# BOTTOM_BRD_v_0_1_0.net
KiCad netlist of a schematic drawn in EAGLE
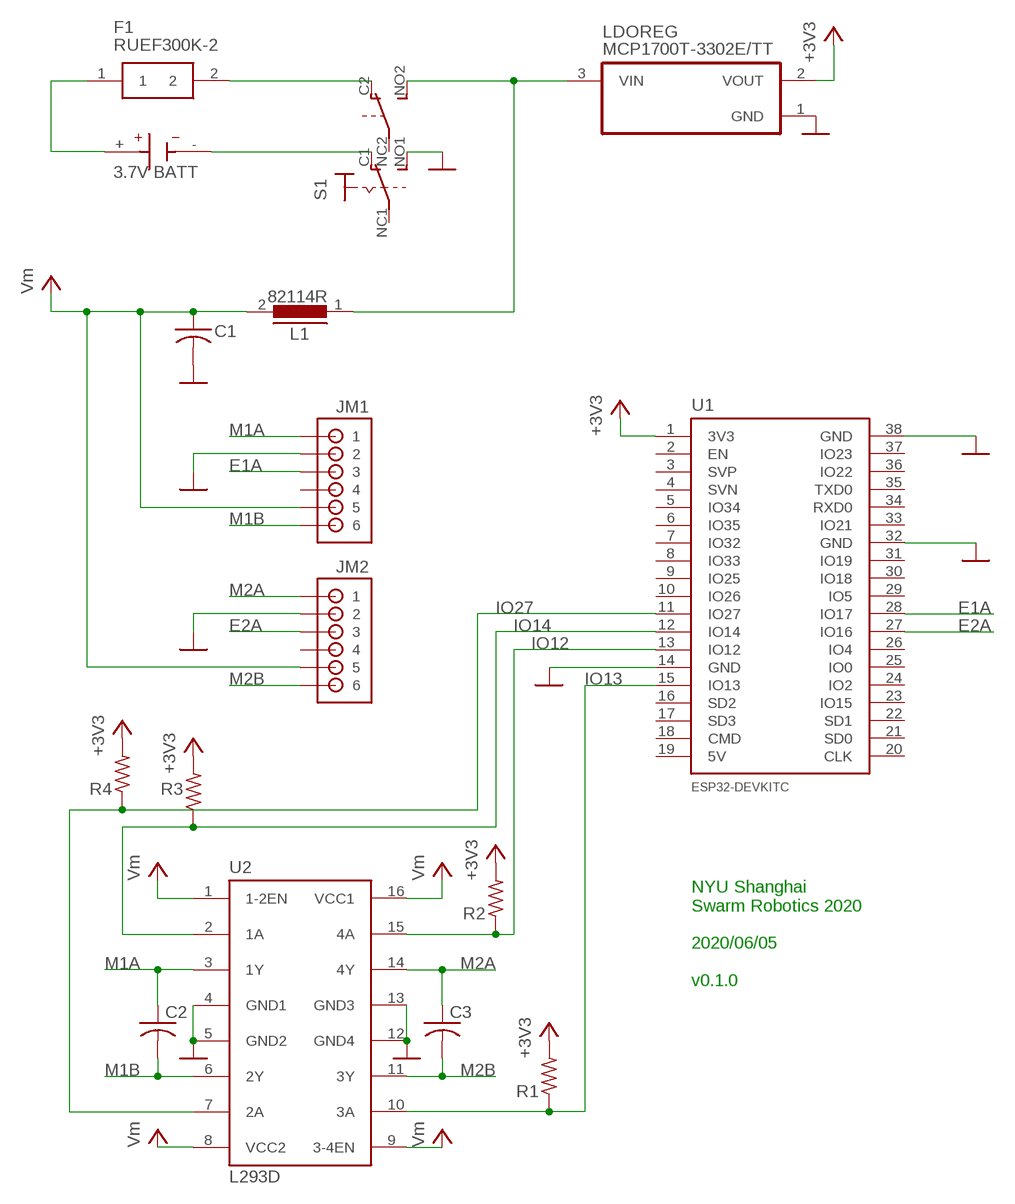
[diagram p0: schematic, sheet 1]

(export (version "E")
  (design (tool "Eeschema 10.0.6"))
  (components
    (comp (ref "BT1")
      (value "3.7V BATT")
      (footprint "eagle-import:BAT_6S-AA")
      (fields (field (name "MF") "MPD") (field (name "MP") "6S-AA"))
      (libsource (lib "eagle-import") (part "6S-AA"))
    )
    (comp (ref "C1")
      (value "C-US025-030X050")
      (footprint "eagle-import:C025-030X050")
      (libsource (lib "eagle-import") (part "C-US025-030X050"))
    )
    (comp (ref "C2")
      (value "C-US025-025X050")
      (footprint "eagle-import:C025-025X050")
      (libsource (lib "eagle-import") (part "C-US025-025X050"))
    )
    (comp (ref "C3")
      (value "C-US025-025X050")
      (footprint "eagle-import:C025-025X050")
      (libsource (lib "eagle-import") (part "C-US025-025X050"))
    )
    (comp (ref "F1")
      (value "RUEF300K-2")
      (footprint "eagle-import:RUEF300K2")
      (libsource (lib "eagle-import") (part "RUEF300K-2"))
    )
    (comp (ref "JM1")
      (value "B6B-ZR")
      (footprint "eagle-import:B6B-ZR")
      (fields (field (name "MF") "JST"))
      (libsource (lib "eagle-import") (part "B6B-ZR"))
    )
    (comp (ref "JM2")
      (value "B6B-ZR")
      (footprint "eagle-import:B6B-ZR")
      (fields (field (name "MF") "JST"))
      (libsource (lib "eagle-import") (part "B6B-ZR"))
    )
    (comp (ref "L1")
      (value "82114R")
      (footprint "eagle-import:82114R")
      (libsource (lib "eagle-import") (part "82114R"))
    )
    (comp (ref "LDOREG")
      (value "MCP1700T-3302E/TT")
      (footprint "eagle-import:SOT95P237X112-3N")
      (fields (field (name "MF") "Microchip Technology"))
      (libsource (lib "eagle-import") (part "MCP1700T-3302E/TT"))
    )
    (comp (ref "R1")
      (value "R-US_0207/9")
      (footprint "eagle-import:0207_9")
      (libsource (lib "eagle-import") (part "R-US_0207/9"))
    )
    (comp (ref "R2")
      (value "R-US_0207/9")
      (footprint "eagle-import:0207_9")
      (libsource (lib "eagle-import") (part "R-US_0207/9"))
    )
    (comp (ref "R3")
      (value "R-US_0207/9")
      (footprint "eagle-import:0207_9")
      (libsource (lib "eagle-import") (part "R-US_0207/9"))
    )
    (comp (ref "R4")
      (value "R-US_0207/9")
      (footprint "eagle-import:0207_9")
      (libsource (lib "eagle-import") (part "R-US_0207/9"))
    )
    (comp (ref "S1")
      (value "SWITCH_320-938")
      (footprint "eagle-import:PS22F03")
      (libsource (lib "eagle-import") (part "SWITCH_320-938"))
    )
    (comp (ref "U1")
      (value "ESP32DEVKITC")
      (footprint "eagle-import:ESP32-DEVKITC")
      (libsource (lib "eagle-import") (part "ESP32DEVKITC"))
    )
    (comp (ref "U2")
      (value "L293D")
      (footprint "eagle-import:DIL16")
      (libsource (lib "eagle-import") (part "L293D"))
    )
  )
  (nets
    (net (code "1") (name "+3V3") (class "Default")
      (node (ref "LDOREG") (pin "2") (pinfunction "VOUT_2") (pintype "output"))
      (node (ref "R1") (pin "2") (pinfunction "2_2") (pintype "passive"))
      (node (ref "R2") (pin "2") (pinfunction "2_2") (pintype "passive"))
      (node (ref "R3") (pin "2") (pinfunction "2_2") (pintype "passive"))
      (node (ref "R4") (pin "2") (pinfunction "2_2") (pintype "passive"))
      (node (ref "U1") (pin "1") (pinfunction "3V3_1") (pintype "bidirectional"))
    )
    (net (code "2") (name "/E1A") (class "Default")
      (node (ref "JM1") (pin "3") (pinfunction "3_3") (pintype "bidirectional"))
      (node (ref "U1") (pin "28") (pinfunction "IO17_28") (pintype "bidirectional"))
    )
    (net (code "3") (name "/E2A") (class "Default")
      (node (ref "JM2") (pin "3") (pinfunction "3_3") (pintype "bidirectional"))
      (node (ref "U1") (pin "27") (pinfunction "IO16_27") (pintype "bidirectional"))
    )
    (net (code "4") (name "/IO12") (class "Default")
      (node (ref "R2") (pin "1") (pinfunction "1_1") (pintype "passive"))
      (node (ref "U1") (pin "13") (pinfunction "IO12_13") (pintype "bidirectional"))
      (node (ref "U2") (pin "15") (pinfunction "4A_15") (pintype "input"))
    )
    (net (code "5") (name "/IO13") (class "Default")
      (node (ref "R1") (pin "1") (pinfunction "1_1") (pintype "passive"))
      (node (ref "U1") (pin "15") (pinfunction "IO13_15") (pintype "bidirectional"))
      (node (ref "U2") (pin "10") (pinfunction "3A_10") (pintype "input"))
    )
    (net (code "6") (name "/IO14") (class "Default")
      (node (ref "R3") (pin "1") (pinfunction "1_1") (pintype "passive"))
      (node (ref "U1") (pin "12") (pinfunction "IO14_12") (pintype "bidirectional"))
      (node (ref "U2") (pin "2") (pinfunction "1A_2") (pintype "input"))
    )
    (net (code "7") (name "/IO27") (class "Default")
      (node (ref "R4") (pin "1") (pinfunction "1_1") (pintype "passive"))
      (node (ref "U1") (pin "11") (pinfunction "IO27_11") (pintype "bidirectional"))
      (node (ref "U2") (pin "7") (pinfunction "2A_7") (pintype "input"))
    )
    (net (code "8") (name "/M1A") (class "Default")
      (node (ref "C2") (pin "1") (pinfunction "1_1") (pintype "passive"))
      (node (ref "JM1") (pin "1") (pinfunction "1_1") (pintype "bidirectional"))
      (node (ref "U2") (pin "3") (pinfunction "1Y_3") (pintype "output"))
    )
    (net (code "9") (name "/M1B") (class "Default")
      (node (ref "C2") (pin "2") (pinfunction "2_2") (pintype "passive"))
      (node (ref "JM1") (pin "6") (pinfunction "6_6") (pintype "bidirectional"))
      (node (ref "U2") (pin "6") (pinfunction "2Y_6") (pintype "output"))
    )
    (net (code "10") (name "/M2A") (class "Default")
      (node (ref "C3") (pin "1") (pinfunction "1_1") (pintype "passive"))
      (node (ref "JM2") (pin "1") (pinfunction "1_1") (pintype "bidirectional"))
      (node (ref "U2") (pin "14") (pinfunction "4Y_14") (pintype "output"))
    )
    (net (code "11") (name "/M2B") (class "Default")
      (node (ref "C3") (pin "2") (pinfunction "2_2") (pintype "passive"))
      (node (ref "JM2") (pin "6") (pinfunction "6_6") (pintype "bidirectional"))
      (node (ref "U2") (pin "11") (pinfunction "3Y_11") (pintype "output"))
    )
    (net (code "12") (name "GND") (class "Default")
      (node (ref "C1") (pin "2") (pinfunction "2_2") (pintype "passive"))
      (node (ref "JM1") (pin "2") (pinfunction "2_2") (pintype "bidirectional"))
      (node (ref "JM2") (pin "2") (pinfunction "2_2") (pintype "bidirectional"))
      (node (ref "LDOREG") (pin "1") (pinfunction "GND_1") (pintype "power_in"))
      (node (ref "S1") (pin "NO1") (pinfunction "S_NO1") (pintype "passive"))
      (node (ref "U1") (pin "14") (pinfunction "GND_14") (pintype "bidirectional"))
      (node (ref "U1") (pin "32") (pinfunction "GND_32") (pintype "bidirectional"))
      (node (ref "U1") (pin "38") (pinfunction "GND_38") (pintype "bidirectional"))
      (node (ref "U2") (pin "12") (pinfunction "GND4_12") (pintype "power_in"))
      (node (ref "U2") (pin "13") (pinfunction "GND3_13") (pintype "power_in"))
      (node (ref "U2") (pin "4") (pinfunction "GND1_4") (pintype "power_in"))
      (node (ref "U2") (pin "5") (pinfunction "GND2_5") (pintype "power_in"))
    )
    (net (code "13") (name "Net-(BT1-Pad+)") (class "Default")
      (node (ref "BT1") (pin "+") (pinfunction "+_+") (pintype "passive"))
      (node (ref "F1") (pin "1") (pinfunction "1_1") (pintype "bidirectional"))
    )
    (net (code "14") (name "Net-(LDOREG-VIN)") (class "Default")
      (node (ref "L1") (pin "1") (pinfunction "1_1") (pintype "passive"))
      (node (ref "LDOREG") (pin "3") (pinfunction "VIN_3") (pintype "input"))
      (node (ref "S1") (pin "NO2") (pinfunction "S_NO2") (pintype "passive"))
    )
    (net (code "15") (name "Net-(S1A-O)") (class "Default")
      (node (ref "BT1") (pin "-") (pinfunction "-_-") (pintype "passive"))
      (node (ref "S1") (pin "C1") (pinfunction "O_C1") (pintype "passive"))
    )
    (net (code "16") (name "Net-(S1B-O)") (class "Default")
      (node (ref "F1") (pin "2") (pinfunction "2_2") (pintype "bidirectional"))
      (node (ref "S1") (pin "C2") (pinfunction "O_C2") (pintype "passive"))
    )
    (net (code "17") (name "Vm") (class "Default")
      (node (ref "C1") (pin "1") (pinfunction "1_1") (pintype "passive"))
      (node (ref "JM1") (pin "5") (pinfunction "5_5") (pintype "bidirectional"))
      (node (ref "JM2") (pin "5") (pinfunction "5_5") (pintype "bidirectional"))
      (node (ref "L1") (pin "2") (pinfunction "2_2") (pintype "passive"))
      (node (ref "U2") (pin "1") (pinfunction "1-2EN_1") (pintype "input"))
      (node (ref "U2") (pin "16") (pinfunction "VCC1_16") (pintype "power_in"))
      (node (ref "U2") (pin "8") (pinfunction "VCC2_8") (pintype "power_in"))
      (node (ref "U2") (pin "9") (pinfunction "3-4EN_9") (pintype "input"))
    )
    (net (code "18") (name "unconnected-(JM1-Pad4)") (class "Default")
      (node (ref "JM1") (pin "4") (pinfunction "4_4") (pintype "bidirectional"))
    )
    (net (code "19") (name "unconnected-(JM2-Pad4)") (class "Default")
      (node (ref "JM2") (pin "4") (pinfunction "4_4") (pintype "bidirectional"))
    )
    (net (code "20") (name "unconnected-(S1A-P-PadNC1)") (class "Default")
      (node (ref "S1") (pin "NC1") (pinfunction "P_NC1") (pintype "passive"))
    )
    (net (code "21") (name "unconnected-(S1B-P-PadNC2)") (class "Default")
      (node (ref "S1") (pin "NC2") (pinfunction "P_NC2") (pintype "passive"))
    )
    (net (code "22") (name "unconnected-(U1-5V-Pad19)") (class "Default")
      (node (ref "U1") (pin "19") (pinfunction "5V_19") (pintype "bidirectional"))
    )
    (net (code "23") (name "unconnected-(U1-CLK-Pad20)") (class "Default")
      (node (ref "U1") (pin "20") (pinfunction "CLK_20") (pintype "bidirectional"))
    )
    (net (code "24") (name "unconnected-(U1-CMD-Pad18)") (class "Default")
      (node (ref "U1") (pin "18") (pinfunction "CMD_18") (pintype "bidirectional"))
    )
    (net (code "25") (name "unconnected-(U1-EN-Pad2)") (class "Default")
      (node (ref "U1") (pin "2") (pinfunction "EN_2") (pintype "bidirectional"))
    )
    (net (code "26") (name "unconnected-(U1-IO0-Pad25)") (class "Default")
      (node (ref "U1") (pin "25") (pinfunction "IO0_25") (pintype "bidirectional"))
    )
    (net (code "27") (name "unconnected-(U1-IO2-Pad24)") (class "Default")
      (node (ref "U1") (pin "24") (pinfunction "IO2_24") (pintype "bidirectional"))
    )
    (net (code "28") (name "unconnected-(U1-IO4-Pad26)") (class "Default")
      (node (ref "U1") (pin "26") (pinfunction "IO4_26") (pintype "bidirectional"))
    )
    (net (code "29") (name "unconnected-(U1-IO5-Pad29)") (class "Default")
      (node (ref "U1") (pin "29") (pinfunction "IO5_29") (pintype "bidirectional"))
    )
    (net (code "30") (name "unconnected-(U1-IO15-Pad23)") (class "Default")
      (node (ref "U1") (pin "23") (pinfunction "IO15_23") (pintype "bidirectional"))
    )
    (net (code "31") (name "unconnected-(U1-IO18-Pad30)") (class "Default")
      (node (ref "U1") (pin "30") (pinfunction "IO18_30") (pintype "bidirectional"))
    )
    (net (code "32") (name "unconnected-(U1-IO19-Pad31)") (class "Default")
      (node (ref "U1") (pin "31") (pinfunction "IO19_31") (pintype "bidirectional"))
    )
    (net (code "33") (name "unconnected-(U1-IO21-Pad33)") (class "Default")
      (node (ref "U1") (pin "33") (pinfunction "IO21_33") (pintype "bidirectional"))
    )
    (net (code "34") (name "unconnected-(U1-IO22-Pad36)") (class "Default")
      (node (ref "U1") (pin "36") (pinfunction "IO22_36") (pintype "bidirectional"))
    )
    (net (code "35") (name "unconnected-(U1-IO23-Pad37)") (class "Default")
      (node (ref "U1") (pin "37") (pinfunction "IO23_37") (pintype "bidirectional"))
    )
    (net (code "36") (name "unconnected-(U1-IO25-Pad9)") (class "Default")
      (node (ref "U1") (pin "9") (pinfunction "IO25_9") (pintype "bidirectional"))
    )
    (net (code "37") (name "unconnected-(U1-IO26-Pad10)") (class "Default")
      (node (ref "U1") (pin "10") (pinfunction "IO26_10") (pintype "bidirectional"))
    )
    (net (code "38") (name "unconnected-(U1-IO32-Pad7)") (class "Default")
      (node (ref "U1") (pin "7") (pinfunction "IO32_7") (pintype "bidirectional"))
    )
    (net (code "39") (name "unconnected-(U1-IO33-Pad8)") (class "Default")
      (node (ref "U1") (pin "8") (pinfunction "IO33_8") (pintype "bidirectional"))
    )
    (net (code "40") (name "unconnected-(U1-IO34-Pad5)") (class "Default")
      (node (ref "U1") (pin "5") (pinfunction "IO34_5") (pintype "bidirectional"))
    )
    (net (code "41") (name "unconnected-(U1-IO35-Pad6)") (class "Default")
      (node (ref "U1") (pin "6") (pinfunction "IO35_6") (pintype "bidirectional"))
    )
    (net (code "42") (name "unconnected-(U1-RXD0-Pad34)") (class "Default")
      (node (ref "U1") (pin "34") (pinfunction "RXD0_34") (pintype "bidirectional"))
    )
    (net (code "43") (name "unconnected-(U1-SD0-Pad21)") (class "Default")
      (node (ref "U1") (pin "21") (pinfunction "SD0_21") (pintype "bidirectional"))
    )
    (net (code "44") (name "unconnected-(U1-SD1-Pad22)") (class "Default")
      (node (ref "U1") (pin "22") (pinfunction "SD1_22") (pintype "bidirectional"))
    )
    (net (code "45") (name "unconnected-(U1-SD2-Pad16)") (class "Default")
      (node (ref "U1") (pin "16") (pinfunction "SD2_16") (pintype "bidirectional"))
    )
    (net (code "46") (name "unconnected-(U1-SD3-Pad17)") (class "Default")
      (node (ref "U1") (pin "17") (pinfunction "SD3_17") (pintype "bidirectional"))
    )
    (net (code "47") (name "unconnected-(U1-SVN-Pad4)") (class "Default")
      (node (ref "U1") (pin "4") (pinfunction "SVN_4") (pintype "bidirectional"))
    )
    (net (code "48") (name "unconnected-(U1-SVP-Pad3)") (class "Default")
      (node (ref "U1") (pin "3") (pinfunction "SVP_3") (pintype "bidirectional"))
    )
    (net (code "49") (name "unconnected-(U1-TXD0-Pad35)") (class "Default")
      (node (ref "U1") (pin "35") (pinfunction "TXD0_35") (pintype "bidirectional"))
    )
  )
)
